# new_inverter.net
KiCad netlist of a schematic drawn in EAGLE
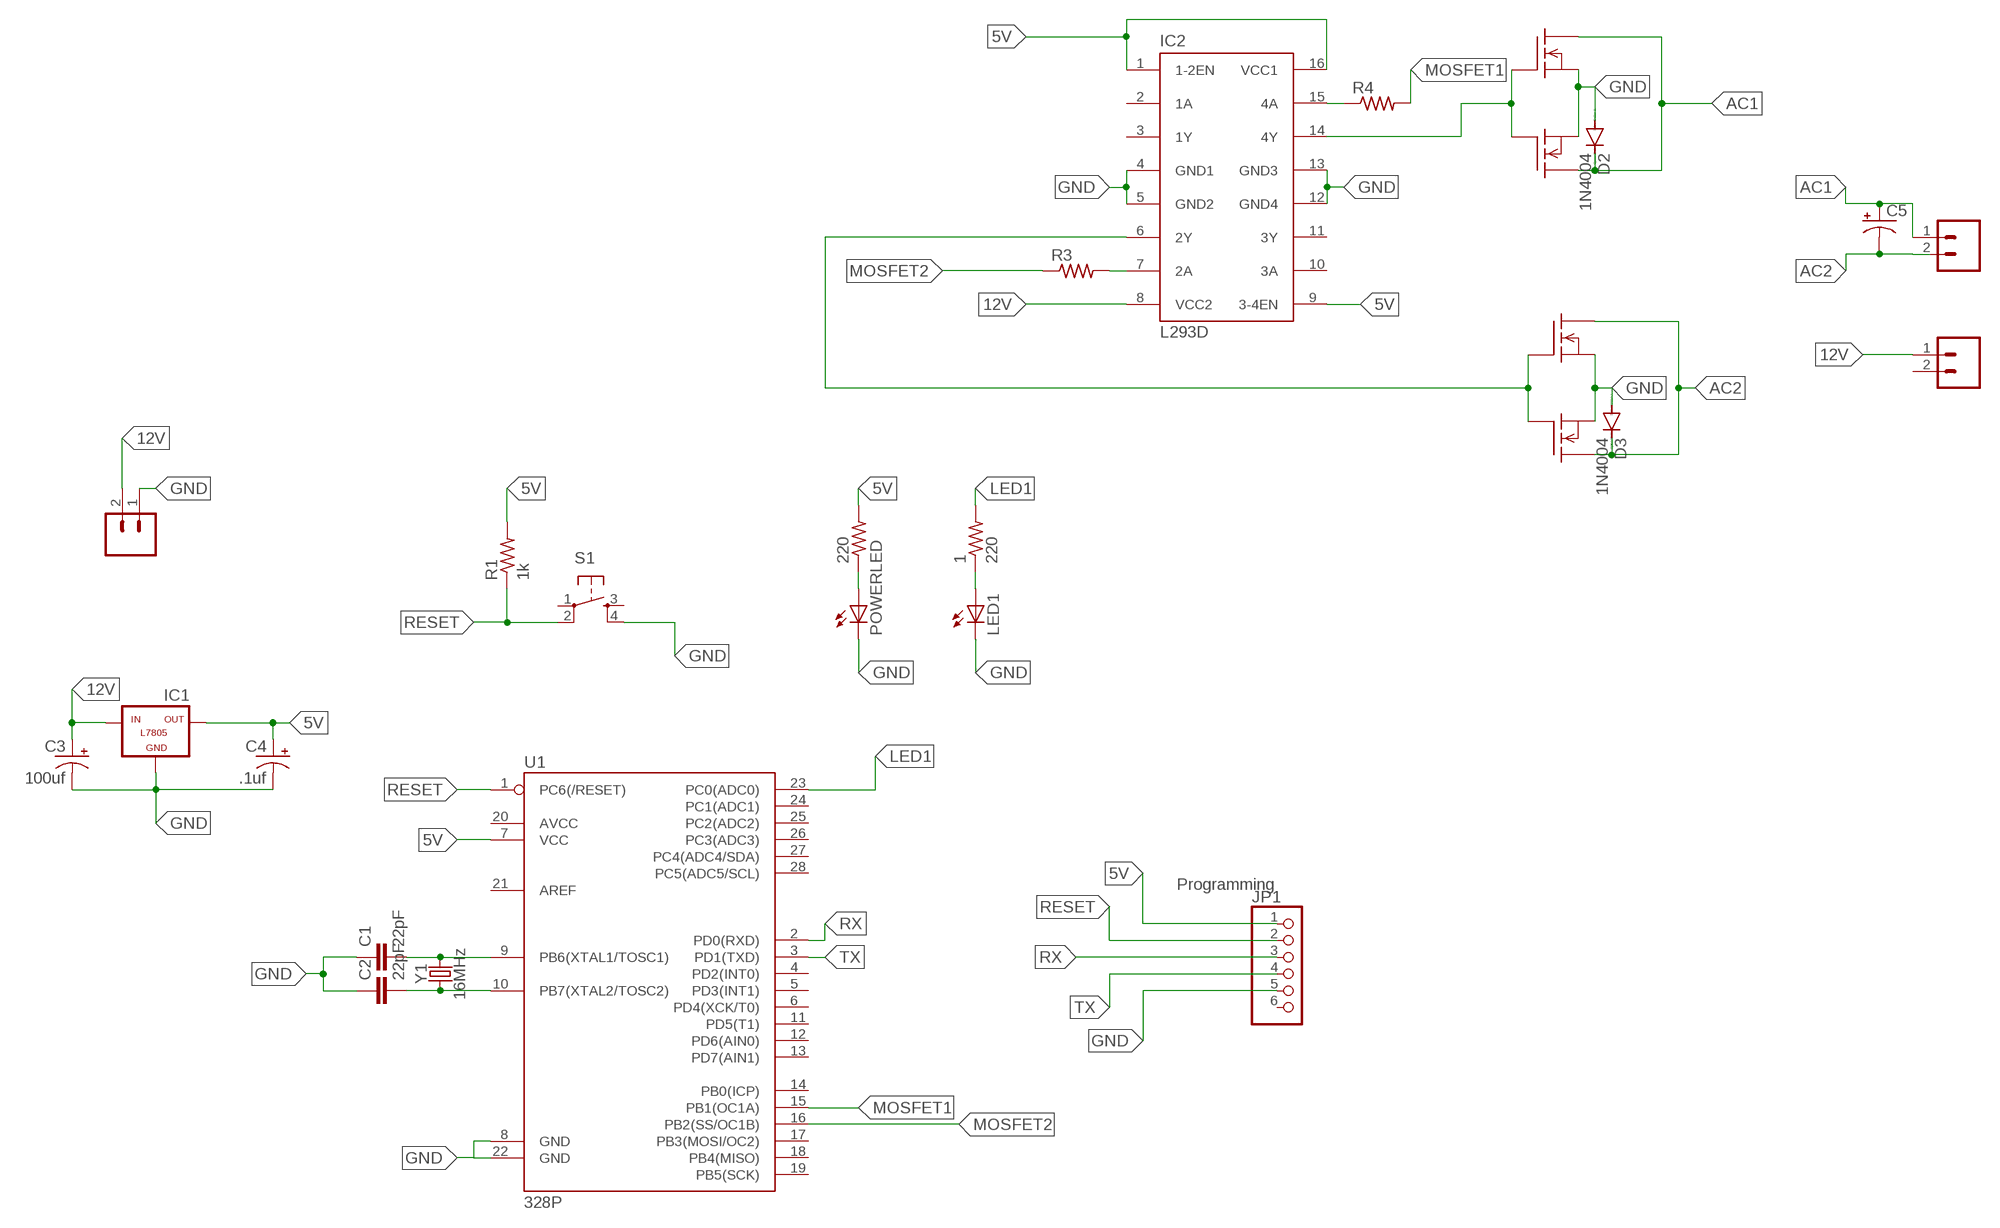
[diagram p0: schematic, sheet 1]

(export (version "E")
  (design (tool "Eeschema 10.0.6"))
  (components
    (comp (ref "1")
      (value "220")
      (footprint "eagle-import:0204_5")
      (libsource (lib "eagle-import") (part "R-US_0204/5"))
    )
    (comp (ref "220")
      (value "R-US_0204/5")
      (footprint "eagle-import:0204_5")
      (libsource (lib "eagle-import") (part "R-US_0204/5"))
    )
    (comp (ref "C1")
      (value "22pF")
      (footprint "eagle-import:CAP-PTH-2.54")
      (libsource (lib "eagle-import") (part "22PF-PTH-2.54MM-200V-5%"))
    )
    (comp (ref "C2")
      (value "22pF")
      (footprint "eagle-import:CAP-PTH-2.54")
      (libsource (lib "eagle-import") (part "22PF-PTH-2.54MM-200V-5%"))
    )
    (comp (ref "C3")
      (value "100uf")
      (footprint "eagle-import:E5-5")
      (libsource (lib "eagle-import") (part "CPOL-USE5-5"))
    )
    (comp (ref "C4")
      (value ".1uf")
      (footprint "eagle-import:E5-5")
      (libsource (lib "eagle-import") (part "CPOL-USE5-5"))
    )
    (comp (ref "C5")
      (value "CPOL-USE5-13")
      (footprint "eagle-import:E5-13")
      (libsource (lib "eagle-import") (part "CPOL-USE5-13"))
    )
    (comp (ref "D2")
      (value "1N4004")
      (footprint "eagle-import:DO41-10")
      (libsource (lib "eagle-import") (part "1N4004"))
    )
    (comp (ref "D3")
      (value "1N4004")
      (footprint "eagle-import:DO41-10")
      (libsource (lib "eagle-import") (part "1N4004"))
    )
    (comp (ref "IC1")
      (value "L7805")
      (footprint "eagle-import:78XXL")
      (libsource (lib "eagle-import") (part "L7805"))
    )
    (comp (ref "IC2")
      (value "L293D")
      (footprint "eagle-import:DIL16")
      (libsource (lib "eagle-import") (part "L293D"))
    )
    (comp (ref "J1")
      (value "CONN_025MM")
      (footprint "eagle-import:SCREWTERMINAL-5MM-2")
      (libsource (lib "eagle-import") (part "CONN_025MM"))
    )
    (comp (ref "J2")
      (value "CONN_025MM")
      (footprint "eagle-import:SCREWTERMINAL-5MM-2")
      (libsource (lib "eagle-import") (part "CONN_025MM"))
    )
    (comp (ref "J3")
      (value "CONN_025MM")
      (footprint "eagle-import:SCREWTERMINAL-5MM-2")
      (libsource (lib "eagle-import") (part "CONN_025MM"))
    )
    (comp (ref "JP1")
      (value "PINHD-1X6")
      (footprint "eagle-import:1X06")
      (libsource (lib "eagle-import") (part "PINHD-1X6"))
    )
    (comp (ref "LED1")
      (value "LED5MM")
      (footprint "eagle-import:LED5MM")
      (libsource (lib "eagle-import") (part "LED5MM"))
    )
    (comp (ref "POWERLED")
      (value "LED5MM")
      (footprint "eagle-import:LED5MM")
      (libsource (lib "eagle-import") (part "LED5MM"))
    )
    (comp (ref "Q1")
      (value "IRF840")
      (footprint "eagle-import:TO220")
      (libsource (lib "eagle-import") (part "IRF840"))
    )
    (comp (ref "Q2")
      (value "IRF840")
      (footprint "eagle-import:TO220")
      (libsource (lib "eagle-import") (part "IRF840"))
    )
    (comp (ref "Q3")
      (value "IRF840")
      (footprint "eagle-import:TO220")
      (libsource (lib "eagle-import") (part "IRF840"))
    )
    (comp (ref "Q4")
      (value "IRF840")
      (footprint "eagle-import:TO220")
      (libsource (lib "eagle-import") (part "IRF840"))
    )
    (comp (ref "R1")
      (value "1k")
      (footprint "eagle-import:0204_5")
      (libsource (lib "eagle-import") (part "R-US_0204/5"))
    )
    (comp (ref "R3")
      (value "R-US_0204/7")
      (footprint "eagle-import:0204_7")
      (libsource (lib "eagle-import") (part "R-US_0204/7"))
    )
    (comp (ref "R4")
      (value "R-US_0204/7")
      (footprint "eagle-import:0204_7")
      (libsource (lib "eagle-import") (part "R-US_0204/7"))
    )
    (comp (ref "S1")
      (value "TAC_SWITCHPTH")
      (footprint "eagle-import:TACTILE-PTH")
      (libsource (lib "eagle-import") (part "TAC_SWITCHPTH"))
    )
    (comp (ref "U1")
      (value "328P")
      (footprint "eagle-import:DIP28")
      (libsource (lib "eagle-import") (part "ATMEGA328P_PDIP"))
    )
    (comp (ref "Y1")
      (value "16MHz")
      (footprint "eagle-import:HC49US")
      (libsource (lib "eagle-import") (part "CRYSTAL-16MHZPTH-HC49US"))
    )
  )
  (nets
    (net (code "1") (name "5V") (class "Default")
      (node (ref "220") (pin "2") (pinfunction "2_2") (pintype "passive"))
      (node (ref "C4") (pin "+") (pinfunction "+_+") (pintype "passive"))
      (node (ref "IC1") (pin "OUT") (pinfunction "OUT_OUT") (pintype "passive"))
      (node (ref "IC2") (pin "1") (pinfunction "1-2EN_1") (pintype "input"))
      (node (ref "IC2") (pin "16") (pinfunction "VCC1_16") (pintype "power_in"))
      (node (ref "IC2") (pin "9") (pinfunction "3-4EN_9") (pintype "input"))
      (node (ref "JP1") (pin "1") (pinfunction "1_1") (pintype "passive"))
      (node (ref "R1") (pin "2") (pinfunction "2_2") (pintype "passive"))
      (node (ref "U1") (pin "7") (pinfunction "VCC_7") (pintype "bidirectional"))
    )
    (net (code "2") (name "12V") (class "Default")
      (node (ref "C3") (pin "+") (pinfunction "+_+") (pintype "passive"))
      (node (ref "IC1") (pin "IN") (pinfunction "IN_IN") (pintype "input"))
      (node (ref "IC2") (pin "8") (pinfunction "VCC2_8") (pintype "power_in"))
      (node (ref "J1") (pin "2") (pinfunction "2_2") (pintype "passive"))
      (node (ref "J2") (pin "1") (pinfunction "1_1") (pintype "passive"))
    )
    (net (code "3") (name "AC1") (class "Default")
      (node (ref "C5") (pin "+") (pinfunction "+_+") (pintype "passive"))
      (node (ref "D2") (pin "C") (pinfunction "C_C") (pintype "passive"))
      (node (ref "J3") (pin "1") (pinfunction "1_1") (pintype "passive"))
      (node (ref "Q2") (pin "2") (pinfunction "D_2") (pintype "passive"))
      (node (ref "Q3") (pin "2") (pinfunction "D_2") (pintype "passive"))
    )
    (net (code "4") (name "AC2") (class "Default")
      (node (ref "C5") (pin "-") (pinfunction "-_-") (pintype "passive"))
      (node (ref "D3") (pin "C") (pinfunction "C_C") (pintype "passive"))
      (node (ref "J3") (pin "2") (pinfunction "2_2") (pintype "passive"))
      (node (ref "Q1") (pin "2") (pinfunction "D_2") (pintype "passive"))
      (node (ref "Q4") (pin "2") (pinfunction "D_2") (pintype "passive"))
    )
    (net (code "5") (name "GND") (class "Default")
      (node (ref "C1") (pin "1") (pinfunction "1_1") (pintype "passive"))
      (node (ref "C2") (pin "1") (pinfunction "1_1") (pintype "passive"))
      (node (ref "C3") (pin "-") (pinfunction "-_-") (pintype "passive"))
      (node (ref "C4") (pin "-") (pinfunction "-_-") (pintype "passive"))
      (node (ref "D2") (pin "A") (pinfunction "A_A") (pintype "passive"))
      (node (ref "D3") (pin "A") (pinfunction "A_A") (pintype "passive"))
      (node (ref "IC1") (pin "GND") (pinfunction "GND_GND") (pintype "input"))
      (node (ref "IC2") (pin "12") (pinfunction "GND4_12") (pintype "power_in"))
      (node (ref "IC2") (pin "13") (pinfunction "GND3_13") (pintype "power_in"))
      (node (ref "IC2") (pin "4") (pinfunction "GND1_4") (pintype "power_in"))
      (node (ref "IC2") (pin "5") (pinfunction "GND2_5") (pintype "power_in"))
      (node (ref "J1") (pin "1") (pinfunction "1_1") (pintype "passive"))
      (node (ref "JP1") (pin "5") (pinfunction "5_5") (pintype "passive"))
      (node (ref "LED1") (pin "K") (pinfunction "C_K") (pintype "passive"))
      (node (ref "POWERLED") (pin "K") (pinfunction "C_K") (pintype "passive"))
      (node (ref "Q1") (pin "3") (pinfunction "S_3") (pintype "passive"))
      (node (ref "Q2") (pin "3") (pinfunction "S_3") (pintype "passive"))
      (node (ref "Q3") (pin "3") (pinfunction "S_3") (pintype "passive"))
      (node (ref "Q4") (pin "3") (pinfunction "S_3") (pintype "passive"))
      (node (ref "S1") (pin "4") (pinfunction "4_4") (pintype "passive"))
      (node (ref "U1") (pin "22") (pinfunction "GND_22") (pintype "bidirectional"))
      (node (ref "U1") (pin "8") (pinfunction "GND_8") (pintype "bidirectional"))
    )
    (net (code "6") (name "LED1") (class "Default")
      (node (ref "1") (pin "2") (pinfunction "2_2") (pintype "passive"))
      (node (ref "U1") (pin "23") (pinfunction "PC0(ADC0)_23") (pintype "bidirectional"))
    )
    (net (code "7") (name "MOSFET1") (class "Default")
      (node (ref "R4") (pin "2") (pinfunction "2_2") (pintype "passive"))
      (node (ref "U1") (pin "15") (pinfunction "PB1(OC1A)_15") (pintype "bidirectional"))
    )
    (net (code "8") (name "MOSFET2") (class "Default")
      (node (ref "R3") (pin "1") (pinfunction "1_1") (pintype "passive"))
      (node (ref "U1") (pin "16") (pinfunction "PB2(SS/OC1B)_16") (pintype "bidirectional"))
    )
    (net (code "9") (name "Net-(1-Pad1)") (class "Default")
      (node (ref "1") (pin "1") (pinfunction "1_1") (pintype "passive"))
      (node (ref "LED1") (pin "A") (pinfunction "A_A") (pintype "passive"))
    )
    (net (code "10") (name "Net-(220-Pad1)") (class "Default")
      (node (ref "220") (pin "1") (pinfunction "1_1") (pintype "passive"))
      (node (ref "POWERLED") (pin "A") (pinfunction "A_A") (pintype "passive"))
    )
    (net (code "11") (name "Net-(IC2-2A)") (class "Default")
      (node (ref "IC2") (pin "7") (pinfunction "2A_7") (pintype "input"))
      (node (ref "R3") (pin "2") (pinfunction "2_2") (pintype "passive"))
    )
    (net (code "12") (name "Net-(IC2-2Y)") (class "Default")
      (node (ref "IC2") (pin "6") (pinfunction "2Y_6") (pintype "output"))
      (node (ref "Q1") (pin "1") (pinfunction "G_1") (pintype "passive"))
      (node (ref "Q4") (pin "1") (pinfunction "G_1") (pintype "passive"))
    )
    (net (code "13") (name "Net-(IC2-4A)") (class "Default")
      (node (ref "IC2") (pin "15") (pinfunction "4A_15") (pintype "input"))
      (node (ref "R4") (pin "1") (pinfunction "1_1") (pintype "passive"))
    )
    (net (code "14") (name "Net-(IC2-4Y)") (class "Default")
      (node (ref "IC2") (pin "14") (pinfunction "4Y_14") (pintype "output"))
      (node (ref "Q2") (pin "1") (pinfunction "G_1") (pintype "passive"))
      (node (ref "Q3") (pin "1") (pinfunction "G_1") (pintype "passive"))
    )
    (net (code "15") (name "Net-(U1-PB6(XTAL1{slash}TOSC1))") (class "Default")
      (node (ref "C1") (pin "2") (pinfunction "2_2") (pintype "passive"))
      (node (ref "U1") (pin "9") (pinfunction "PB6(XTAL1/TOSC1)_9") (pintype "bidirectional"))
      (node (ref "Y1") (pin "2") (pinfunction "2_2") (pintype "passive"))
    )
    (net (code "16") (name "Net-(U1-PB7(XTAL2{slash}TOSC2))") (class "Default")
      (node (ref "C2") (pin "2") (pinfunction "2_2") (pintype "passive"))
      (node (ref "U1") (pin "10") (pinfunction "PB7(XTAL2/TOSC2)_10") (pintype "bidirectional"))
      (node (ref "Y1") (pin "1") (pinfunction "1_1") (pintype "passive"))
    )
    (net (code "17") (name "RESET") (class "Default")
      (node (ref "JP1") (pin "2") (pinfunction "2_2") (pintype "passive"))
      (node (ref "R1") (pin "1") (pinfunction "1_1") (pintype "passive"))
      (node (ref "S1") (pin "2") (pinfunction "2_2") (pintype "passive"))
      (node (ref "U1") (pin "1") (pinfunction "PC6(/RESET)_1") (pintype "bidirectional"))
    )
    (net (code "18") (name "RX") (class "Default")
      (node (ref "JP1") (pin "3") (pinfunction "3_3") (pintype "passive"))
      (node (ref "U1") (pin "2") (pinfunction "PD0(RXD)_2") (pintype "bidirectional"))
    )
    (net (code "19") (name "TX") (class "Default")
      (node (ref "JP1") (pin "4") (pinfunction "4_4") (pintype "passive"))
      (node (ref "U1") (pin "3") (pinfunction "PD1(TXD)_3") (pintype "bidirectional"))
    )
    (net (code "20") (name "unconnected-(IC2-1A-Pad2)") (class "Default")
      (node (ref "IC2") (pin "2") (pinfunction "1A_2") (pintype "input"))
    )
    (net (code "21") (name "unconnected-(IC2-1Y-Pad3)") (class "Default")
      (node (ref "IC2") (pin "3") (pinfunction "1Y_3") (pintype "output"))
    )
    (net (code "22") (name "unconnected-(IC2-3A-Pad10)") (class "Default")
      (node (ref "IC2") (pin "10") (pinfunction "3A_10") (pintype "input"))
    )
    (net (code "23") (name "unconnected-(IC2-3Y-Pad11)") (class "Default")
      (node (ref "IC2") (pin "11") (pinfunction "3Y_11") (pintype "output"))
    )
    (net (code "24") (name "unconnected-(J2-Pad2)") (class "Default")
      (node (ref "J2") (pin "2") (pinfunction "2_2") (pintype "passive"))
    )
    (net (code "25") (name "unconnected-(JP1-Pad6)") (class "Default")
      (node (ref "JP1") (pin "6") (pinfunction "6_6") (pintype "passive"))
    )
    (net (code "26") (name "unconnected-(S1-Pad1)") (class "Default")
      (node (ref "S1") (pin "1") (pinfunction "1_1") (pintype "passive"))
    )
    (net (code "27") (name "unconnected-(S1-Pad3)") (class "Default")
      (node (ref "S1") (pin "3") (pinfunction "3_3") (pintype "passive"))
    )
    (net (code "28") (name "unconnected-(U1-AREF-Pad21)") (class "Default")
      (node (ref "U1") (pin "21") (pinfunction "AREF_21") (pintype "bidirectional"))
    )
    (net (code "29") (name "unconnected-(U1-AVCC-Pad20)") (class "Default")
      (node (ref "U1") (pin "20") (pinfunction "AVCC_20") (pintype "bidirectional"))
    )
    (net (code "30") (name "unconnected-(U1-PB0(ICP)-Pad14)") (class "Default")
      (node (ref "U1") (pin "14") (pinfunction "PB0(ICP)_14") (pintype "bidirectional"))
    )
    (net (code "31") (name "unconnected-(U1-PB3(MOSI{slash}OC2)-Pad17)") (class "Default")
      (node (ref "U1") (pin "17") (pinfunction "PB3(MOSI/OC2)_17") (pintype "bidirectional"))
    )
    (net (code "32") (name "unconnected-(U1-PB4(MISO)-Pad18)") (class "Default")
      (node (ref "U1") (pin "18") (pinfunction "PB4(MISO)_18") (pintype "bidirectional"))
    )
    (net (code "33") (name "unconnected-(U1-PB5(SCK)-Pad19)") (class "Default")
      (node (ref "U1") (pin "19") (pinfunction "PB5(SCK)_19") (pintype "bidirectional"))
    )
    (net (code "34") (name "unconnected-(U1-PC1(ADC1)-Pad24)") (class "Default")
      (node (ref "U1") (pin "24") (pinfunction "PC1(ADC1)_24") (pintype "bidirectional"))
    )
    (net (code "35") (name "unconnected-(U1-PC2(ADC2)-Pad25)") (class "Default")
      (node (ref "U1") (pin "25") (pinfunction "PC2(ADC2)_25") (pintype "bidirectional"))
    )
    (net (code "36") (name "unconnected-(U1-PC3(ADC3)-Pad26)") (class "Default")
      (node (ref "U1") (pin "26") (pinfunction "PC3(ADC3)_26") (pintype "bidirectional"))
    )
    (net (code "37") (name "unconnected-(U1-PC4(ADC4{slash}SDA)-Pad27)") (class "Default")
      (node (ref "U1") (pin "27") (pinfunction "PC4(ADC4/SDA)_27") (pintype "bidirectional"))
    )
    (net (code "38") (name "unconnected-(U1-PC5(ADC5{slash}SCL)-Pad28)") (class "Default")
      (node (ref "U1") (pin "28") (pinfunction "PC5(ADC5/SCL)_28") (pintype "bidirectional"))
    )
    (net (code "39") (name "unconnected-(U1-PD2(INT0)-Pad4)") (class "Default")
      (node (ref "U1") (pin "4") (pinfunction "PD2(INT0)_4") (pintype "bidirectional"))
    )
    (net (code "40") (name "unconnected-(U1-PD3(INT1)-Pad5)") (class "Default")
      (node (ref "U1") (pin "5") (pinfunction "PD3(INT1)_5") (pintype "bidirectional"))
    )
    (net (code "41") (name "unconnected-(U1-PD4(XCK{slash}T0)-Pad6)") (class "Default")
      (node (ref "U1") (pin "6") (pinfunction "PD4(XCK/T0)_6") (pintype "bidirectional"))
    )
    (net (code "42") (name "unconnected-(U1-PD5(T1)-Pad11)") (class "Default")
      (node (ref "U1") (pin "11") (pinfunction "PD5(T1)_11") (pintype "bidirectional"))
    )
    (net (code "43") (name "unconnected-(U1-PD6(AIN0)-Pad12)") (class "Default")
      (node (ref "U1") (pin "12") (pinfunction "PD6(AIN0)_12") (pintype "bidirectional"))
    )
    (net (code "44") (name "unconnected-(U1-PD7(AIN1)-Pad13)") (class "Default")
      (node (ref "U1") (pin "13") (pinfunction "PD7(AIN1)_13") (pintype "bidirectional"))
    )
  )
)
